# Timer.net
KiCad netlist of a schematic drawn in EAGLE
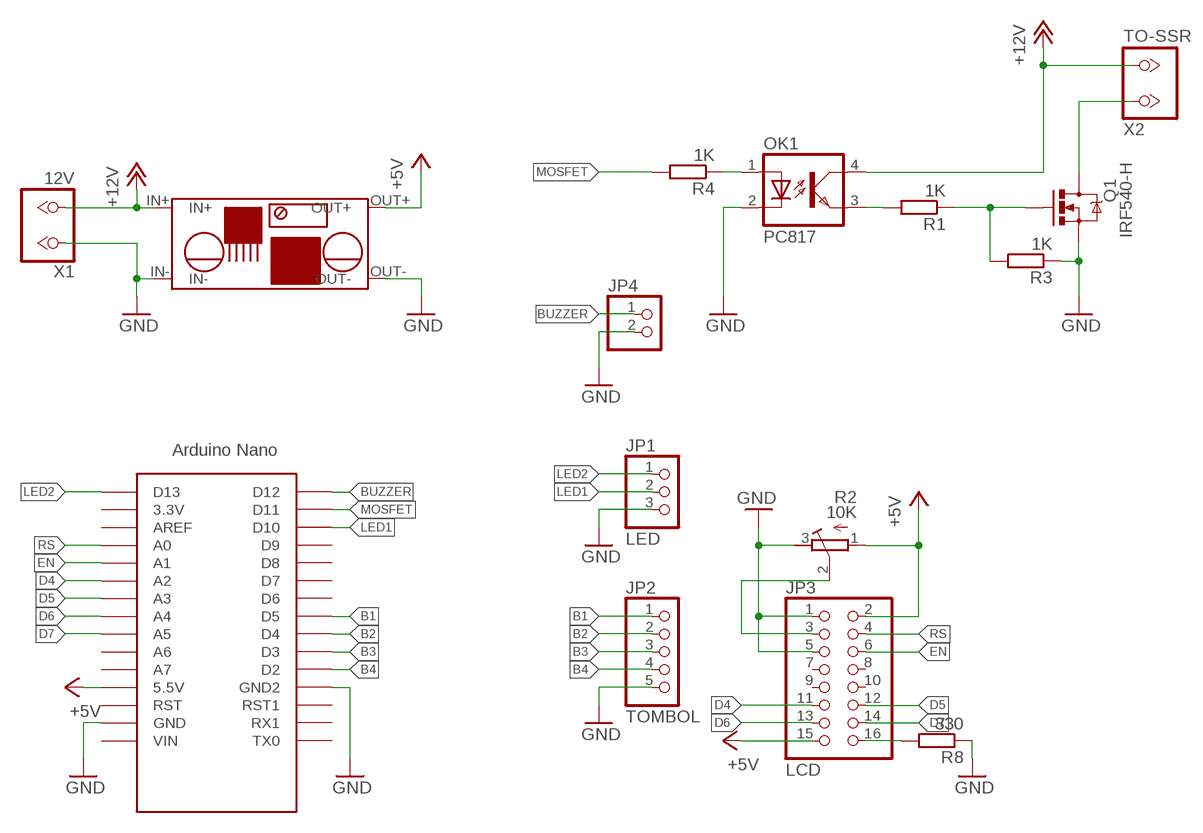
[diagram p0: schematic, sheet 1]

(export (version "E")
  (design (tool "Eeschema 10.0.6"))
  (components
    (comp (ref "JP1")
      (value "LED")
      (footprint "eagle-import:1X03")
      (libsource (lib "eagle-import") (part "PINHD-1X3"))
    )
    (comp (ref "JP2")
      (value "TOMBOL")
      (footprint "eagle-import:1X05")
      (libsource (lib "eagle-import") (part "PINHD-1X5{dblquote}"))
    )
    (comp (ref "JP3")
      (value "LCD")
      (footprint "eagle-import:2X08")
      (libsource (lib "eagle-import") (part "PINHD-2X8"))
    )
    (comp (ref "JP4")
      (value "PINHD-1X2")
      (footprint "eagle-import:1X02")
      (libsource (lib "eagle-import") (part "PINHD-1X2"))
    )
    (comp (ref "MOD1")
      (value "LM2576")
      (footprint "eagle-import:LM2576")
      (libsource (lib "eagle-import") (part "LM2576"))
    )
    (comp (ref "OK1")
      (value "PC817")
      (footprint "eagle-import:DIL04")
      (fields (field (name "MPN") "PC817X4J000F"))
      (libsource (lib "eagle-import") (part "PC817"))
    )
    (comp (ref "Q1")
      (value "IRF540-H")
      (footprint "eagle-import:TO-220H")
      (libsource (lib "eagle-import") (part "IRF540-H"))
    )
    (comp (ref "R1")
      (value "1K")
      (footprint "eagle-import:0207_7")
      (libsource (lib "eagle-import") (part "R-EU_0207/7"))
    )
    (comp (ref "R2")
      (value "10K")
      (footprint "eagle-import:RTRIM3339")
      (libsource (lib "eagle-import") (part "R-TRIMM3339"))
    )
    (comp (ref "R3")
      (value "1K")
      (footprint "eagle-import:0207_7")
      (libsource (lib "eagle-import") (part "R-EU_0207/7"))
    )
    (comp (ref "R4")
      (value "1K")
      (footprint "eagle-import:0207_7")
      (libsource (lib "eagle-import") (part "R-EU_0207/7"))
    )
    (comp (ref "R8")
      (value "330")
      (footprint "eagle-import:0207_7")
      (libsource (lib "eagle-import") (part "R-EU_0207/7"))
    )
    (comp (ref "U$1")
      (value "NANO")
      (footprint "eagle-import:NANO")
      (libsource (lib "eagle-import") (part "NANO"))
    )
    (comp (ref "X1")
      (value "12V")
      (footprint "eagle-import:KL2")
      (libsource (lib "eagle-import") (part "2PIN-SCREW"))
    )
    (comp (ref "X2")
      (value "TO-SSR")
      (footprint "eagle-import:KL2")
      (libsource (lib "eagle-import") (part "2PIN-SCREW"))
    )
  )
  (nets
    (net (code "1") (name "+5V") (class "Default")
      (node (ref "JP3") (pin "15") (pinfunction "15_15") (pintype "passive"))
      (node (ref "JP3") (pin "2") (pinfunction "2_2") (pintype "passive"))
      (node (ref "MOD1") (pin "OUT+") (pinfunction "OUT+_OUT+") (pintype "bidirectional"))
      (node (ref "R2") (pin "1") (pinfunction "A_1") (pintype "passive"))
      (node (ref "U$1") (pin "5V") (pinfunction "5.5V_5V") (pintype "bidirectional"))
    )
    (net (code "2") (name "+12V") (class "Default")
      (node (ref "MOD1") (pin "IN+") (pinfunction "IN+_IN+") (pintype "bidirectional"))
      (node (ref "OK1") (pin "4") (pinfunction "COL_4") (pintype "passive"))
      (node (ref "X1") (pin "2") (pinfunction "2_2") (pintype "bidirectional"))
      (node (ref "X2") (pin "2") (pinfunction "2_2") (pintype "bidirectional"))
    )
    (net (code "3") (name "B1") (class "Default")
      (node (ref "JP2") (pin "1") (pinfunction "1_1") (pintype "passive"))
      (node (ref "U$1") (pin "D5") (pinfunction "D5_D5") (pintype "bidirectional"))
    )
    (net (code "4") (name "B2") (class "Default")
      (node (ref "JP2") (pin "2") (pinfunction "2_2") (pintype "passive"))
      (node (ref "U$1") (pin "D4") (pinfunction "D4_D4") (pintype "bidirectional"))
    )
    (net (code "5") (name "B3") (class "Default")
      (node (ref "JP2") (pin "3") (pinfunction "3_3") (pintype "passive"))
      (node (ref "U$1") (pin "D3") (pinfunction "D3_D3") (pintype "bidirectional"))
    )
    (net (code "6") (name "B4") (class "Default")
      (node (ref "JP2") (pin "4") (pinfunction "4_4") (pintype "passive"))
      (node (ref "U$1") (pin "D2") (pinfunction "D2_D2") (pintype "bidirectional"))
    )
    (net (code "7") (name "BUZZER") (class "Default")
      (node (ref "JP4") (pin "1") (pinfunction "1_1") (pintype "passive"))
      (node (ref "U$1") (pin "D12") (pinfunction "D12_D12") (pintype "bidirectional"))
    )
    (net (code "8") (name "D4") (class "Default")
      (node (ref "JP3") (pin "11") (pinfunction "11_11") (pintype "passive"))
      (node (ref "U$1") (pin "A2") (pinfunction "A2_A2") (pintype "bidirectional"))
    )
    (net (code "9") (name "D5") (class "Default")
      (node (ref "JP3") (pin "12") (pinfunction "12_12") (pintype "passive"))
      (node (ref "U$1") (pin "A3") (pinfunction "A3_A3") (pintype "bidirectional"))
    )
    (net (code "10") (name "D6") (class "Default")
      (node (ref "JP3") (pin "13") (pinfunction "13_13") (pintype "passive"))
      (node (ref "U$1") (pin "A4") (pinfunction "A4_A4") (pintype "bidirectional"))
    )
    (net (code "11") (name "D7") (class "Default")
      (node (ref "JP3") (pin "14") (pinfunction "14_14") (pintype "passive"))
      (node (ref "U$1") (pin "A5") (pinfunction "A5_A5") (pintype "bidirectional"))
    )
    (net (code "12") (name "EN") (class "Default")
      (node (ref "JP3") (pin "6") (pinfunction "6_6") (pintype "passive"))
      (node (ref "U$1") (pin "A1") (pinfunction "A1_A1") (pintype "bidirectional"))
    )
    (net (code "13") (name "GND") (class "Default")
      (node (ref "JP1") (pin "3") (pinfunction "3_3") (pintype "passive"))
      (node (ref "JP2") (pin "5") (pinfunction "5_5") (pintype "passive"))
      (node (ref "JP3") (pin "1") (pinfunction "1_1") (pintype "passive"))
      (node (ref "JP3") (pin "5") (pinfunction "5_5") (pintype "passive"))
      (node (ref "JP4") (pin "2") (pinfunction "2_2") (pintype "passive"))
      (node (ref "MOD1") (pin "IN-") (pinfunction "IN-_IN-") (pintype "bidirectional"))
      (node (ref "MOD1") (pin "OUT-") (pinfunction "OUT-_OUT-") (pintype "bidirectional"))
      (node (ref "OK1") (pin "2") (pinfunction "C_2") (pintype "passive"))
      (node (ref "Q1") (pin "3") (pinfunction "S_3") (pintype "passive"))
      (node (ref "R2") (pin "3") (pinfunction "E_3") (pintype "passive"))
      (node (ref "R3") (pin "1") (pinfunction "1_1") (pintype "passive"))
      (node (ref "R8") (pin "1") (pinfunction "1_1") (pintype "passive"))
      (node (ref "U$1") (pin "GND") (pinfunction "GND_GND") (pintype "bidirectional"))
      (node (ref "U$1") (pin "GND1") (pinfunction "GND2_GND1") (pintype "bidirectional"))
      (node (ref "X1") (pin "1") (pinfunction "1_1") (pintype "bidirectional"))
    )
    (net (code "14") (name "LED1") (class "Default")
      (node (ref "JP1") (pin "2") (pinfunction "2_2") (pintype "passive"))
      (node (ref "U$1") (pin "D10") (pinfunction "D10_D10") (pintype "bidirectional"))
    )
    (net (code "15") (name "LED2") (class "Default")
      (node (ref "JP1") (pin "1") (pinfunction "1_1") (pintype "passive"))
      (node (ref "U$1") (pin "D13") (pinfunction "D13_D13") (pintype "bidirectional"))
    )
    (net (code "16") (name "MOSFET") (class "Default")
      (node (ref "R4") (pin "2") (pinfunction "2_2") (pintype "passive"))
      (node (ref "U$1") (pin "D11") (pinfunction "D11_D11") (pintype "bidirectional"))
    )
    (net (code "17") (name "Net-(JP3-Pad16)") (class "Default")
      (node (ref "JP3") (pin "16") (pinfunction "16_16") (pintype "passive"))
      (node (ref "R8") (pin "2") (pinfunction "2_2") (pintype "passive"))
    )
    (net (code "18") (name "Net-(OK1-A)") (class "Default")
      (node (ref "OK1") (pin "1") (pinfunction "A_1") (pintype "passive"))
      (node (ref "R4") (pin "1") (pinfunction "1_1") (pintype "passive"))
    )
    (net (code "19") (name "Net-(OK1-EMIT)") (class "Default")
      (node (ref "OK1") (pin "3") (pinfunction "EMIT_3") (pintype "passive"))
      (node (ref "R1") (pin "2") (pinfunction "2_2") (pintype "passive"))
    )
    (net (code "20") (name "Net-(Q1-D)") (class "Default")
      (node (ref "Q1") (pin "2") (pinfunction "D_2") (pintype "passive"))
      (node (ref "X2") (pin "1") (pinfunction "1_1") (pintype "bidirectional"))
    )
    (net (code "21") (name "Net-(Q1-G)") (class "Default")
      (node (ref "Q1") (pin "1") (pinfunction "G_1") (pintype "passive"))
      (node (ref "R1") (pin "1") (pinfunction "1_1") (pintype "passive"))
      (node (ref "R3") (pin "2") (pinfunction "2_2") (pintype "passive"))
    )
    (net (code "22") (name "Net-(R2-S)") (class "Default")
      (node (ref "JP3") (pin "3") (pinfunction "3_3") (pintype "passive"))
      (node (ref "R2") (pin "2") (pinfunction "S_2") (pintype "passive"))
    )
    (net (code "23") (name "RS") (class "Default")
      (node (ref "JP3") (pin "4") (pinfunction "4_4") (pintype "passive"))
      (node (ref "U$1") (pin "A0") (pinfunction "A0_A0") (pintype "bidirectional"))
    )
    (net (code "24") (name "unconnected-(JP3-Pad7)") (class "Default")
      (node (ref "JP3") (pin "7") (pinfunction "7_7") (pintype "passive"))
    )
    (net (code "25") (name "unconnected-(JP3-Pad8)") (class "Default")
      (node (ref "JP3") (pin "8") (pinfunction "8_8") (pintype "passive"))
    )
    (net (code "26") (name "unconnected-(JP3-Pad9)") (class "Default")
      (node (ref "JP3") (pin "9") (pinfunction "9_9") (pintype "passive"))
    )
    (net (code "27") (name "unconnected-(JP3-Pad10)") (class "Default")
      (node (ref "JP3") (pin "10") (pinfunction "10_10") (pintype "passive"))
    )
    (net (code "28") (name "unconnected-(U$1-Pad3.3V)") (class "Default")
      (node (ref "U$1") (pin "3.3V") (pinfunction "3.3V_3.3V") (pintype "bidirectional"))
    )
    (net (code "29") (name "unconnected-(U$1-PadA6)") (class "Default")
      (node (ref "U$1") (pin "A6") (pinfunction "A6_A6") (pintype "bidirectional"))
    )
    (net (code "30") (name "unconnected-(U$1-PadA7)") (class "Default")
      (node (ref "U$1") (pin "A7") (pinfunction "A7_A7") (pintype "bidirectional"))
    )
    (net (code "31") (name "unconnected-(U$1-PadAREF)") (class "Default")
      (node (ref "U$1") (pin "AREF") (pinfunction "AREF_AREF") (pintype "bidirectional"))
    )
    (net (code "32") (name "unconnected-(U$1-PadD6)") (class "Default")
      (node (ref "U$1") (pin "D6") (pinfunction "D6_D6") (pintype "bidirectional"))
    )
    (net (code "33") (name "unconnected-(U$1-PadD7)") (class "Default")
      (node (ref "U$1") (pin "D7") (pinfunction "D7_D7") (pintype "bidirectional"))
    )
    (net (code "34") (name "unconnected-(U$1-PadD8)") (class "Default")
      (node (ref "U$1") (pin "D8") (pinfunction "D8_D8") (pintype "bidirectional"))
    )
    (net (code "35") (name "unconnected-(U$1-PadD9)") (class "Default")
      (node (ref "U$1") (pin "D9") (pinfunction "D9_D9") (pintype "bidirectional"))
    )
    (net (code "36") (name "unconnected-(U$1-PadRST)") (class "Default")
      (node (ref "U$1") (pin "RST") (pinfunction "RST_RST") (pintype "bidirectional"))
    )
    (net (code "37") (name "unconnected-(U$1-PadRST1)") (class "Default")
      (node (ref "U$1") (pin "RST1") (pinfunction "RST1_RST1") (pintype "bidirectional"))
    )
    (net (code "38") (name "unconnected-(U$1-PadRX1)") (class "Default")
      (node (ref "U$1") (pin "RX1") (pinfunction "RX1_RX1") (pintype "bidirectional"))
    )
    (net (code "39") (name "unconnected-(U$1-PadTX0)") (class "Default")
      (node (ref "U$1") (pin "TX0") (pinfunction "TX0_TX0") (pintype "bidirectional"))
    )
    (net (code "40") (name "unconnected-(U$1-PadVIN)") (class "Default")
      (node (ref "U$1") (pin "VIN") (pinfunction "VIN_VIN") (pintype "bidirectional"))
    )
  )
)
